# tinyLight.net
KiCad netlist of a schematic drawn in EAGLE
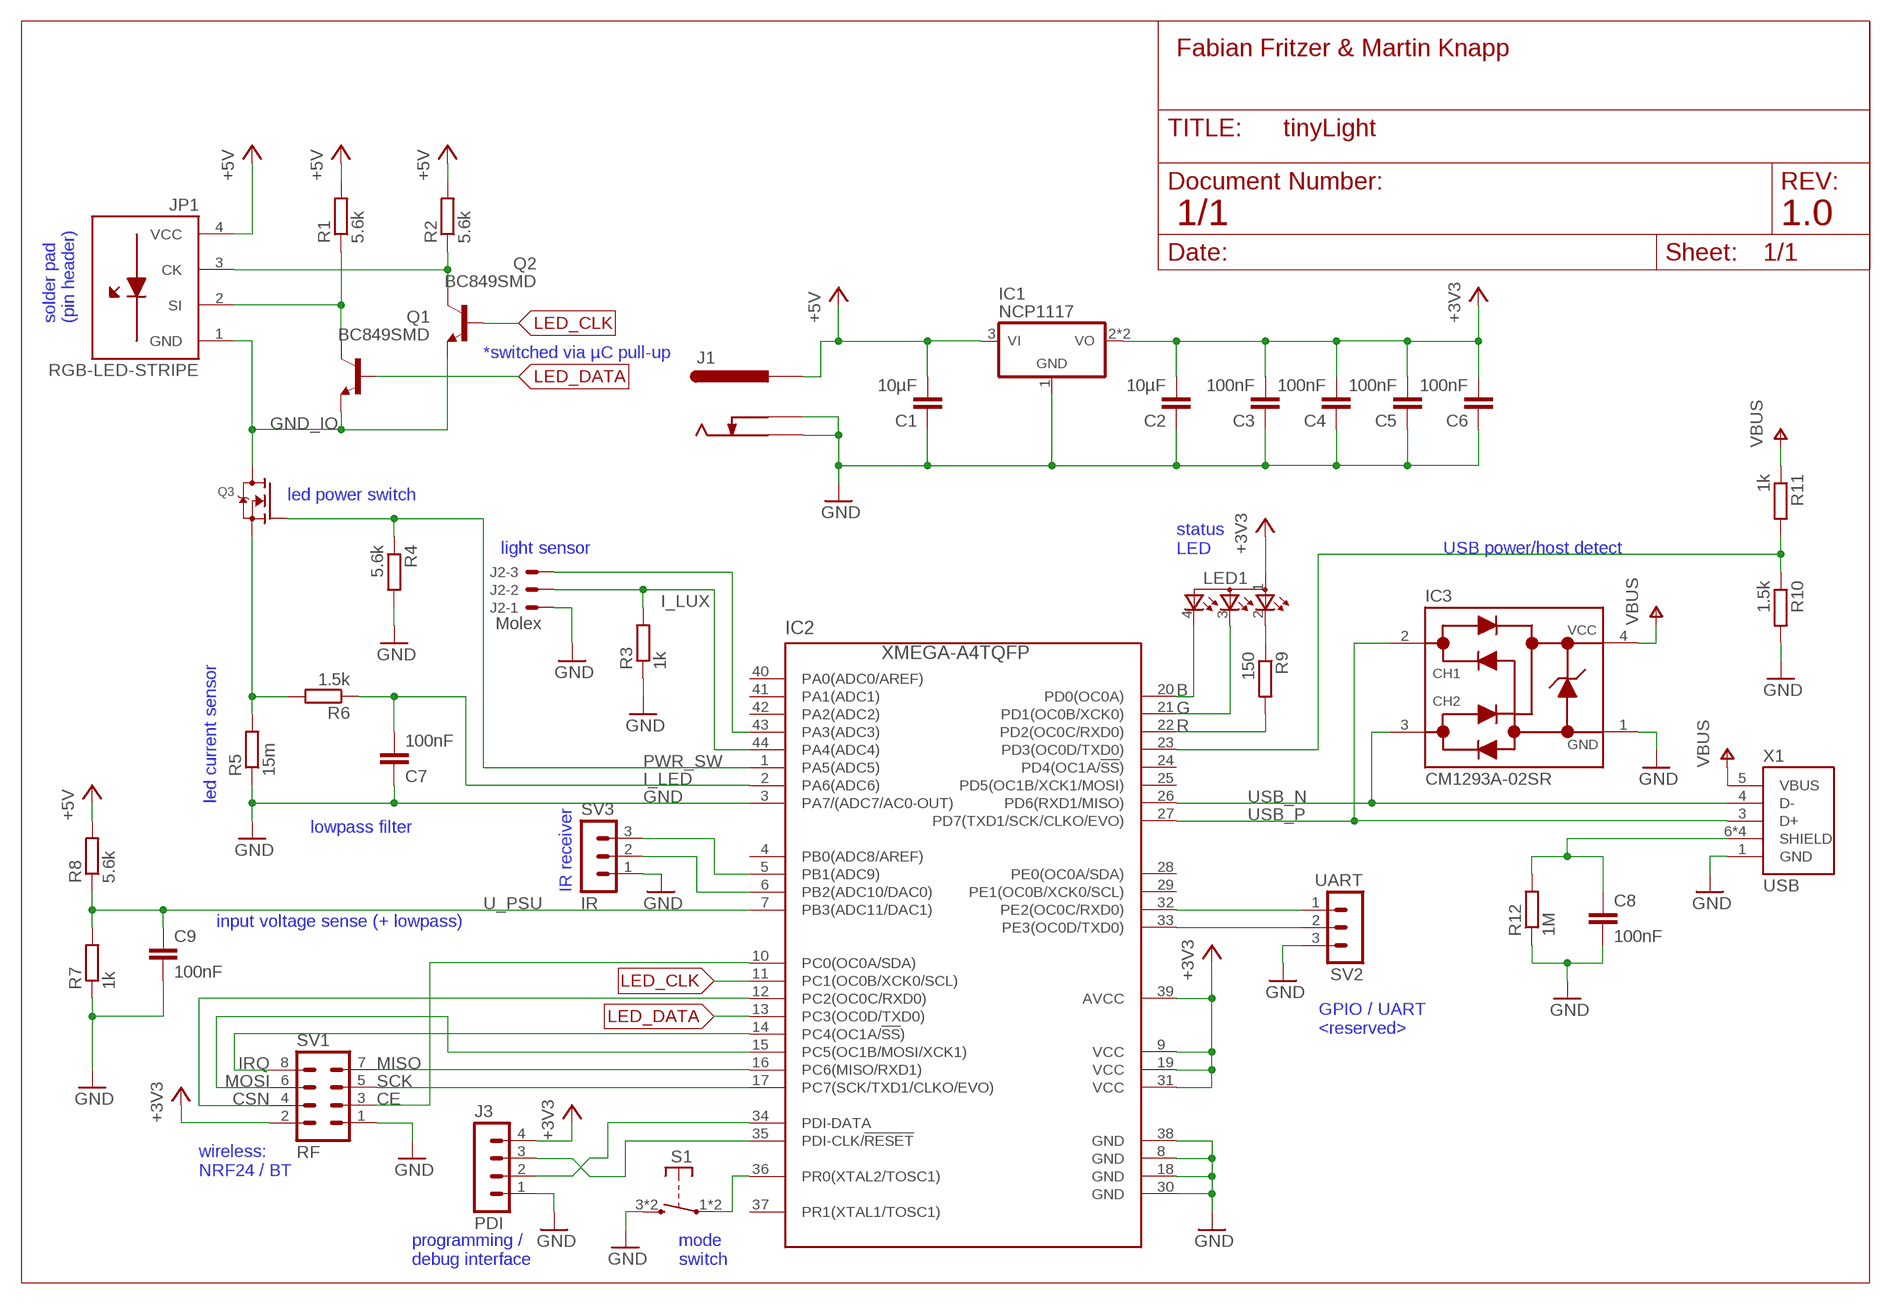
[diagram p0: schematic, sheet 1]

(export (version "E")
  (design (tool "Eeschema 10.0.6"))
  (components
    (comp (ref "C1")
      (value "10µF")
      (footprint "eagle-import:C2012")
      (libsource (lib "eagle-import") (part "C-EUC2012"))
    )
    (comp (ref "C2")
      (value "10µF")
      (footprint "eagle-import:C2012")
      (libsource (lib "eagle-import") (part "C-EUC2012"))
    )
    (comp (ref "C3")
      (value "100nF")
      (footprint "eagle-import:C2012")
      (libsource (lib "eagle-import") (part "C-EUC2012"))
    )
    (comp (ref "C4")
      (value "100nF")
      (footprint "eagle-import:C2012")
      (libsource (lib "eagle-import") (part "C-EUC2012"))
    )
    (comp (ref "C5")
      (value "100nF")
      (footprint "eagle-import:C2012")
      (libsource (lib "eagle-import") (part "C-EUC2012"))
    )
    (comp (ref "C6")
      (value "100nF")
      (footprint "eagle-import:C2012")
      (libsource (lib "eagle-import") (part "C-EUC2012"))
    )
    (comp (ref "C7")
      (value "100nF")
      (footprint "eagle-import:C2012")
      (libsource (lib "eagle-import") (part "C-EUC2012"))
    )
    (comp (ref "C8")
      (value "100nF")
      (footprint "eagle-import:C2012")
      (libsource (lib "eagle-import") (part "C-EUC2012"))
    )
    (comp (ref "C9")
      (value "100nF")
      (footprint "eagle-import:C2012")
      (libsource (lib "eagle-import") (part "C-EUC2012"))
    )
    (comp (ref "IC1")
      (value "NCP1117")
      (footprint "eagle-import:SOT223")
      (libsource (lib "eagle-import") (part "NCP1117"))
    )
    (comp (ref "IC2")
      (value "XMEGA-A4TQFP")
      (footprint "eagle-import:TQFP44")
      (libsource (lib "eagle-import") (part "XMEGA-A4TQFP"))
    )
    (comp (ref "IC3")
      (value "CM1293A-02SR")
      (footprint "eagle-import:SOT143")
      (libsource (lib "eagle-import") (part "CM1293A-02SR"))
    )
    (comp (ref "J1")
      (value "RASM722PX")
      (footprint "eagle-import:RASM722PX")
      (libsource (lib "eagle-import") (part "RASM722PX"))
    )
    (comp (ref "J2")
      (value "Molex")
      (footprint "eagle-import:6410-03")
      (libsource (lib "eagle-import") (part "22-?-0327-2031"))
    )
    (comp (ref "J3")
      (value "PDI")
      (footprint "eagle-import:MA04-1")
      (libsource (lib "eagle-import") (part "MA04-1"))
    )
    (comp (ref "JP1")
      (value "RGB-LED-STRIPE")
      (footprint "eagle-import:LED-STRIPE")
      (libsource (lib "eagle-import") (part "RGB-LED-STRIPE"))
    )
    (comp (ref "LED1")
      (value "RGB-LEDMINI")
      (footprint "eagle-import:P-LCC-4_M")
      (libsource (lib "eagle-import") (part "RGB-LEDMINI"))
    )
    (comp (ref "Q1")
      (value "BC849SMD")
      (footprint "eagle-import:SOT23-BEC")
      (libsource (lib "eagle-import") (part "BC849SMD"))
    )
    (comp (ref "Q2")
      (value "BC849SMD")
      (footprint "eagle-import:SOT23-BEC")
      (libsource (lib "eagle-import") (part "BC849SMD"))
    )
    (comp (ref "Q3")
      (value "MOSFET-N")
      (footprint "eagle-import:SOT457R_PHILIPS")
      (libsource (lib "eagle-import") (part "MOSFET-N"))
    )
    (comp (ref "R1")
      (value "5.6k")
      (footprint "eagle-import:M2012")
      (libsource (lib "eagle-import") (part "R-EU_M2012"))
    )
    (comp (ref "R2")
      (value "5.6k")
      (footprint "eagle-import:M2012")
      (libsource (lib "eagle-import") (part "R-EU_M2012"))
    )
    (comp (ref "R3")
      (value "1k")
      (footprint "eagle-import:M2012")
      (libsource (lib "eagle-import") (part "R-EU_M2012"))
    )
    (comp (ref "R4")
      (value "5.6k")
      (footprint "eagle-import:M2012")
      (libsource (lib "eagle-import") (part "R-EU_M2012"))
    )
    (comp (ref "R5")
      (value "15m")
      (footprint "eagle-import:M3216")
      (libsource (lib "eagle-import") (part "R-EU_M3216"))
    )
    (comp (ref "R6")
      (value "1.5k")
      (footprint "eagle-import:M2012")
      (libsource (lib "eagle-import") (part "R-EU_M2012"))
    )
    (comp (ref "R7")
      (value "1k")
      (footprint "eagle-import:M2012")
      (libsource (lib "eagle-import") (part "R-EU_M2012"))
    )
    (comp (ref "R8")
      (value "5.6k")
      (footprint "eagle-import:M2012")
      (libsource (lib "eagle-import") (part "R-EU_M2012"))
    )
    (comp (ref "R9")
      (value "150")
      (footprint "eagle-import:M2012")
      (libsource (lib "eagle-import") (part "R-EU_M2012"))
    )
    (comp (ref "R10")
      (value "1.5k")
      (footprint "eagle-import:M2012")
      (libsource (lib "eagle-import") (part "R-EU_M2012"))
    )
    (comp (ref "R11")
      (value "1k")
      (footprint "eagle-import:M2012")
      (libsource (lib "eagle-import") (part "R-EU_M2012"))
    )
    (comp (ref "R12")
      (value "1M")
      (footprint "eagle-import:M2012")
      (libsource (lib "eagle-import") (part "R-EU_M2012"))
    )
    (comp (ref "S1")
      (value "SPST_PB")
      (footprint "eagle-import:LSH_6X6")
      (libsource (lib "eagle-import") (part "SPST_PB"))
    )
    (comp (ref "SV1")
      (value "RF")
      (footprint "eagle-import:MA04-2")
      (libsource (lib "eagle-import") (part "MA04-2"))
    )
    (comp (ref "SV2")
      (value "UART")
      (footprint "eagle-import:MA03-1")
      (libsource (lib "eagle-import") (part "MA03-1"))
    )
    (comp (ref "SV3")
      (value "IR")
      (footprint "eagle-import:MA03-1")
      (libsource (lib "eagle-import") (part "MA03-1"))
    )
    (comp (ref "X1")
      (value "MICRO-USB")
      (footprint "eagle-import:MIKRO_B")
      (libsource (lib "eagle-import") (part "MICRO-USB"))
    )
  )
  (nets
    (net (code "1") (name "+3V3") (class "Default")
      (node (ref "C2") (pin "2") (pinfunction "2_2") (pintype "passive"))
      (node (ref "C3") (pin "2") (pinfunction "2_2") (pintype "passive"))
      (node (ref "C4") (pin "2") (pinfunction "2_2") (pintype "passive"))
      (node (ref "C5") (pin "2") (pinfunction "2_2") (pintype "passive"))
      (node (ref "C6") (pin "2") (pinfunction "2_2") (pintype "passive"))
      (node (ref "IC1") (pin "2") (pinfunction "VOUT_2") (pintype "output"))
      (node (ref "IC1") (pin "T") (pinfunction "VOUT_T") (pintype "output"))
      (node (ref "IC2") (pin "19") (pinfunction "VCC_19") (pintype "power_in"))
      (node (ref "IC2") (pin "31") (pinfunction "VCC_31") (pintype "power_in"))
      (node (ref "IC2") (pin "39") (pinfunction "AVCC_39") (pintype "power_in"))
      (node (ref "IC2") (pin "9") (pinfunction "VCC_9") (pintype "power_in"))
      (node (ref "J3") (pin "4") (pinfunction "4_4") (pintype "passive"))
      (node (ref "LED1") (pin "1") (pinfunction "ANODE_1") (pintype "passive"))
      (node (ref "SV1") (pin "2") (pinfunction "2_2") (pintype "passive"))
    )
    (net (code "2") (name "+5V") (class "Default")
      (node (ref "C1") (pin "2") (pinfunction "2_2") (pintype "passive"))
      (node (ref "IC1") (pin "3") (pinfunction "VIN_3") (pintype "input"))
      (node (ref "J1") (pin "TIP") (pinfunction "TIP_TIP") (pintype "power_in"))
      (node (ref "JP1") (pin "4") (pinfunction "VCC_4") (pintype "power_in"))
      (node (ref "R1") (pin "2") (pinfunction "2_2") (pintype "passive"))
      (node (ref "R2") (pin "2") (pinfunction "2_2") (pintype "passive"))
      (node (ref "R8") (pin "2") (pinfunction "2_2") (pintype "passive"))
    )
    (net (code "3") (name "/B") (class "Default")
      (node (ref "IC2") (pin "20") (pinfunction "PD0(OC0A)_20") (pintype "bidirectional"))
      (node (ref "LED1") (pin "4") (pinfunction "CBLUE_4") (pintype "passive"))
    )
    (net (code "4") (name "/CE") (class "Default")
      (node (ref "IC2") (pin "10") (pinfunction "PC0(OC0A/SDA)_10") (pintype "bidirectional"))
      (node (ref "SV1") (pin "3") (pinfunction "3_3") (pintype "passive"))
    )
    (net (code "5") (name "/CSN") (class "Default")
      (node (ref "IC2") (pin "12") (pinfunction "PC2(OC0C/RXD0)_12") (pintype "bidirectional"))
      (node (ref "SV1") (pin "4") (pinfunction "4_4") (pintype "passive"))
    )
    (net (code "6") (name "/G") (class "Default")
      (node (ref "IC2") (pin "21") (pinfunction "PD1(OC0B/XCK0)_21") (pintype "bidirectional"))
      (node (ref "LED1") (pin "3") (pinfunction "CGREEN_3") (pintype "passive"))
    )
    (net (code "7") (name "/GND_IO") (class "Default")
      (node (ref "JP1") (pin "1") (pinfunction "GND_1") (pintype "power_in"))
      (node (ref "Q1") (pin "E") (pinfunction "E_E") (pintype "passive"))
      (node (ref "Q2") (pin "E") (pinfunction "E_E") (pintype "passive"))
      (node (ref "Q3") (pin "1") (pinfunction "D_1") (pintype "passive"))
      (node (ref "Q3") (pin "2") (pinfunction "D_2") (pintype "passive"))
      (node (ref "Q3") (pin "5") (pinfunction "D_5") (pintype "passive"))
      (node (ref "Q3") (pin "6") (pinfunction "D_6") (pintype "passive"))
    )
    (net (code "8") (name "/IRQ") (class "Default")
      (node (ref "IC2") (pin "14") (pinfunction "PC4(OC1A/~{SS})_14") (pintype "bidirectional"))
      (node (ref "SV1") (pin "8") (pinfunction "8_8") (pintype "passive"))
    )
    (net (code "9") (name "/I_LED") (class "Default")
      (node (ref "C7") (pin "2") (pinfunction "2_2") (pintype "passive"))
      (node (ref "IC2") (pin "2") (pinfunction "PA6(ADC6)_2") (pintype "bidirectional"))
      (node (ref "R6") (pin "1") (pinfunction "1_1") (pintype "passive"))
    )
    (net (code "10") (name "/I_LUX") (class "Default")
      (node (ref "IC2") (pin "44") (pinfunction "PA4(ADC4)_44") (pintype "bidirectional"))
      (node (ref "J2") (pin "2") (pinfunction "S_2") (pintype "passive"))
      (node (ref "R3") (pin "2") (pinfunction "2_2") (pintype "passive"))
    )
    (net (code "11") (name "/MISO") (class "Default")
      (node (ref "IC2") (pin "16") (pinfunction "PC6(MISO/RXD1)_16") (pintype "bidirectional"))
      (node (ref "SV1") (pin "7") (pinfunction "7_7") (pintype "passive"))
    )
    (net (code "12") (name "/MOSI") (class "Default")
      (node (ref "IC2") (pin "15") (pinfunction "PC5(OC1B/MOSI/XCK1)_15") (pintype "bidirectional"))
      (node (ref "SV1") (pin "6") (pinfunction "6_6") (pintype "passive"))
    )
    (net (code "13") (name "/PWR_SW") (class "Default")
      (node (ref "IC2") (pin "1") (pinfunction "PA5(ADC5)_1") (pintype "bidirectional"))
      (node (ref "Q3") (pin "3") (pinfunction "G_3") (pintype "passive"))
      (node (ref "R4") (pin "1") (pinfunction "1_1") (pintype "passive"))
    )
    (net (code "14") (name "/R") (class "Default")
      (node (ref "IC2") (pin "22") (pinfunction "PD2(OC0C/RXD0)_22") (pintype "bidirectional"))
      (node (ref "R9") (pin "2") (pinfunction "2_2") (pintype "passive"))
    )
    (net (code "15") (name "/SCK") (class "Default")
      (node (ref "IC2") (pin "17") (pinfunction "PC7(SCK/TXD1/CLKO/EVO)_17") (pintype "bidirectional"))
      (node (ref "SV1") (pin "5") (pinfunction "5_5") (pintype "passive"))
    )
    (net (code "16") (name "/USB_N") (class "Default")
      (node (ref "IC2") (pin "26") (pinfunction "PD6(RXD1/MISO)_26") (pintype "bidirectional"))
      (node (ref "IC3") (pin "3") (pinfunction "CH2_3") (pintype "bidirectional"))
      (node (ref "X1") (pin "4") (pinfunction "D-_4") (pintype "bidirectional"))
    )
    (net (code "17") (name "/USB_P") (class "Default")
      (node (ref "IC2") (pin "27") (pinfunction "PD7(TXD1/SCK/CLKO/EVO)_27") (pintype "bidirectional"))
      (node (ref "IC3") (pin "2") (pinfunction "CH1_2") (pintype "bidirectional"))
      (node (ref "X1") (pin "3") (pinfunction "D+_3") (pintype "bidirectional"))
    )
    (net (code "18") (name "/U_PSU") (class "Default")
      (node (ref "C9") (pin "1") (pinfunction "1_1") (pintype "passive"))
      (node (ref "IC2") (pin "7") (pinfunction "PB3(ADC11/DAC1)_7") (pintype "bidirectional"))
      (node (ref "R7") (pin "2") (pinfunction "2_2") (pintype "passive"))
      (node (ref "R8") (pin "1") (pinfunction "1_1") (pintype "passive"))
    )
    (net (code "19") (name "GND") (class "Default")
      (node (ref "C1") (pin "1") (pinfunction "1_1") (pintype "passive"))
      (node (ref "C2") (pin "1") (pinfunction "1_1") (pintype "passive"))
      (node (ref "C3") (pin "1") (pinfunction "1_1") (pintype "passive"))
      (node (ref "C4") (pin "1") (pinfunction "1_1") (pintype "passive"))
      (node (ref "C5") (pin "1") (pinfunction "1_1") (pintype "passive"))
      (node (ref "C6") (pin "1") (pinfunction "1_1") (pintype "passive"))
      (node (ref "C7") (pin "1") (pinfunction "1_1") (pintype "passive"))
      (node (ref "C8") (pin "2") (pinfunction "2_2") (pintype "passive"))
      (node (ref "C9") (pin "2") (pinfunction "2_2") (pintype "passive"))
      (node (ref "IC1") (pin "1") (pinfunction "GND_1") (pintype "power_in"))
      (node (ref "IC2") (pin "18") (pinfunction "GND_18") (pintype "power_in"))
      (node (ref "IC2") (pin "3") (pinfunction "PA7/(ADC7/AC0-OUT)_3") (pintype "bidirectional"))
      (node (ref "IC2") (pin "30") (pinfunction "GND_30") (pintype "power_in"))
      (node (ref "IC2") (pin "38") (pinfunction "GND_38") (pintype "power_in"))
      (node (ref "IC2") (pin "8") (pinfunction "GND_8") (pintype "power_in"))
      (node (ref "IC3") (pin "1") (pinfunction "GND_1") (pintype "power_in"))
      (node (ref "J1") (pin "SHUNT") (pinfunction "SHUNT_SHUNT") (pintype "power_in"))
      (node (ref "J1") (pin "SLEEVE") (pinfunction "SLEVE_SLEEVE") (pintype "bidirectional"))
      (node (ref "J2") (pin "1") (pinfunction "S_1") (pintype "passive"))
      (node (ref "J3") (pin "1") (pinfunction "1_1") (pintype "passive"))
      (node (ref "R10") (pin "2") (pinfunction "2_2") (pintype "passive"))
      (node (ref "R12") (pin "1") (pinfunction "1_1") (pintype "passive"))
      (node (ref "R3") (pin "1") (pinfunction "1_1") (pintype "passive"))
      (node (ref "R4") (pin "2") (pinfunction "2_2") (pintype "passive"))
      (node (ref "R5") (pin "1") (pinfunction "1_1") (pintype "passive"))
      (node (ref "R7") (pin "1") (pinfunction "1_1") (pintype "passive"))
      (node (ref "S1") (pin "3") (pinfunction "2_3") (pintype "passive"))
      (node (ref "S1") (pin "4") (pinfunction "2_4") (pintype "passive"))
      (node (ref "SV1") (pin "1") (pinfunction "1_1") (pintype "passive"))
      (node (ref "SV2") (pin "3") (pinfunction "3_3") (pintype "passive"))
      (node (ref "SV3") (pin "1") (pinfunction "1_1") (pintype "passive"))
      (node (ref "X1") (pin "1") (pinfunction "GND_1") (pintype "power_in"))
    )
    (net (code "20") (name "LED_CLK") (class "Default")
      (node (ref "IC2") (pin "11") (pinfunction "PC1(OC0B/XCK0/SCL)_11") (pintype "bidirectional"))
      (node (ref "Q2") (pin "B") (pinfunction "B_B") (pintype "passive"))
    )
    (net (code "21") (name "LED_DATA") (class "Default")
      (node (ref "IC2") (pin "13") (pinfunction "PC3(OC0D/TXD0)_13") (pintype "bidirectional"))
      (node (ref "Q1") (pin "B") (pinfunction "B_B") (pintype "passive"))
    )
    (net (code "22") (name "Net-(C8-Pad1)") (class "Default")
      (node (ref "C8") (pin "1") (pinfunction "1_1") (pintype "passive"))
      (node (ref "R12") (pin "2") (pinfunction "2_2") (pintype "passive"))
      (node (ref "X1") (pin "6") (pinfunction "SHIELD_6") (pintype "bidirectional"))
      (node (ref "X1") (pin "7") (pinfunction "SHIELD_7") (pintype "bidirectional"))
      (node (ref "X1") (pin "8") (pinfunction "SHIELD_8") (pintype "bidirectional"))
      (node (ref "X1") (pin "9") (pinfunction "SHIELD_9") (pintype "bidirectional"))
    )
    (net (code "23") (name "Net-(IC2-PA3(ADC3))") (class "Default")
      (node (ref "IC2") (pin "43") (pinfunction "PA3(ADC3)_43") (pintype "bidirectional"))
      (node (ref "J2") (pin "3") (pinfunction "S_3") (pintype "passive"))
    )
    (net (code "24") (name "Net-(IC2-PB1(ADC9))") (class "Default")
      (node (ref "IC2") (pin "5") (pinfunction "PB1(ADC9)_5") (pintype "bidirectional"))
      (node (ref "SV3") (pin "3") (pinfunction "3_3") (pintype "passive"))
    )
    (net (code "25") (name "Net-(IC2-PB2(ADC10{slash}DAC0))") (class "Default")
      (node (ref "IC2") (pin "6") (pinfunction "PB2(ADC10/DAC0)_6") (pintype "bidirectional"))
      (node (ref "SV3") (pin "2") (pinfunction "2_2") (pintype "passive"))
    )
    (net (code "26") (name "Net-(IC2-PD3(OC0D{slash}TXD0))") (class "Default")
      (node (ref "IC2") (pin "23") (pinfunction "PD3(OC0D/TXD0)_23") (pintype "bidirectional"))
      (node (ref "R10") (pin "1") (pinfunction "1_1") (pintype "passive"))
      (node (ref "R11") (pin "2") (pinfunction "2_2") (pintype "passive"))
    )
    (net (code "27") (name "Net-(IC2-PDI-CLK{slash}~{RESET})") (class "Default")
      (node (ref "IC2") (pin "35") (pinfunction "PDI-CLK/~{RESET}_35") (pintype "input"))
      (node (ref "J3") (pin "3") (pinfunction "3_3") (pintype "passive"))
    )
    (net (code "28") (name "Net-(IC2-PDI-DATA)") (class "Default")
      (node (ref "IC2") (pin "34") (pinfunction "PDI-DATA_34") (pintype "bidirectional"))
      (node (ref "J3") (pin "2") (pinfunction "2_2") (pintype "passive"))
    )
    (net (code "29") (name "Net-(IC2-PE2(OC0C{slash}RXD0))") (class "Default")
      (node (ref "IC2") (pin "32") (pinfunction "PE2(OC0C/RXD0)_32") (pintype "bidirectional"))
      (node (ref "SV2") (pin "1") (pinfunction "1_1") (pintype "passive"))
    )
    (net (code "30") (name "Net-(IC2-PE3(OC0D{slash}TXD0))") (class "Default")
      (node (ref "IC2") (pin "33") (pinfunction "PE3(OC0D/TXD0)_33") (pintype "bidirectional"))
      (node (ref "SV2") (pin "2") (pinfunction "2_2") (pintype "passive"))
    )
    (net (code "31") (name "Net-(IC2-PR0(XTAL2{slash}TOSC1))") (class "Default")
      (node (ref "IC2") (pin "36") (pinfunction "PR0(XTAL2/TOSC1)_36") (pintype "bidirectional"))
      (node (ref "S1") (pin "1") (pinfunction "1_1") (pintype "passive"))
      (node (ref "S1") (pin "2") (pinfunction "1_2") (pintype "passive"))
    )
    (net (code "32") (name "Net-(JP1-CK)") (class "Default")
      (node (ref "JP1") (pin "3") (pinfunction "CK_3") (pintype "input"))
      (node (ref "Q2") (pin "C") (pinfunction "C_C") (pintype "passive"))
      (node (ref "R2") (pin "1") (pinfunction "1_1") (pintype "passive"))
    )
    (net (code "33") (name "Net-(JP1-SI)") (class "Default")
      (node (ref "JP1") (pin "2") (pinfunction "SI_2") (pintype "input"))
      (node (ref "Q1") (pin "C") (pinfunction "C_C") (pintype "passive"))
      (node (ref "R1") (pin "1") (pinfunction "1_1") (pintype "passive"))
    )
    (net (code "34") (name "Net-(LED1-CRED)") (class "Default")
      (node (ref "LED1") (pin "2") (pinfunction "CRED_2") (pintype "passive"))
      (node (ref "R9") (pin "1") (pinfunction "1_1") (pintype "passive"))
    )
    (net (code "35") (name "Net-(Q3-S)") (class "Default")
      (node (ref "Q3") (pin "4") (pinfunction "S_4") (pintype "passive"))
      (node (ref "R5") (pin "2") (pinfunction "2_2") (pintype "passive"))
      (node (ref "R6") (pin "2") (pinfunction "2_2") (pintype "passive"))
    )
    (net (code "36") (name "VBUS") (class "Default")
      (node (ref "IC3") (pin "4") (pinfunction "VCC_4") (pintype "power_in"))
      (node (ref "R11") (pin "1") (pinfunction "1_1") (pintype "passive"))
      (node (ref "X1") (pin "5") (pinfunction "VBUS_5") (pintype "bidirectional"))
    )
    (net (code "37") (name "unconnected-(IC2-PA0(ADC0{slash}AREF)-Pad40)") (class "Default")
      (node (ref "IC2") (pin "40") (pinfunction "PA0(ADC0/AREF)_40") (pintype "bidirectional"))
    )
    (net (code "38") (name "unconnected-(IC2-PA1(ADC1)-Pad41)") (class "Default")
      (node (ref "IC2") (pin "41") (pinfunction "PA1(ADC1)_41") (pintype "bidirectional"))
    )
    (net (code "39") (name "unconnected-(IC2-PA2(ADC2)-Pad42)") (class "Default")
      (node (ref "IC2") (pin "42") (pinfunction "PA2(ADC2)_42") (pintype "bidirectional"))
    )
    (net (code "40") (name "unconnected-(IC2-PB0(ADC8{slash}AREF)-Pad4)") (class "Default")
      (node (ref "IC2") (pin "4") (pinfunction "PB0(ADC8/AREF)_4") (pintype "bidirectional"))
    )
    (net (code "41") (name "unconnected-(IC2-PD4(OC1A{slash}~{SS})-Pad24)") (class "Default")
      (node (ref "IC2") (pin "24") (pinfunction "PD4(OC1A/~{SS})_24") (pintype "bidirectional"))
    )
    (net (code "42") (name "unconnected-(IC2-PD5(OC1B{slash}XCK1{slash}MOSI)-Pad25)") (class "Default")
      (node (ref "IC2") (pin "25") (pinfunction "PD5(OC1B/XCK1/MOSI)_25") (pintype "bidirectional"))
    )
    (net (code "43") (name "unconnected-(IC2-PE0(OC0A{slash}SDA)-Pad28)") (class "Default")
      (node (ref "IC2") (pin "28") (pinfunction "PE0(OC0A/SDA)_28") (pintype "bidirectional"))
    )
    (net (code "44") (name "unconnected-(IC2-PE1(OC0B{slash}XCK0{slash}SCL)-Pad29)") (class "Default")
      (node (ref "IC2") (pin "29") (pinfunction "PE1(OC0B/XCK0/SCL)_29") (pintype "bidirectional"))
    )
    (net (code "45") (name "unconnected-(IC2-PR1(XTAL1{slash}TOSC1)-Pad37)") (class "Default")
      (node (ref "IC2") (pin "37") (pinfunction "PR1(XTAL1/TOSC1)_37") (pintype "bidirectional"))
    )
  )
)
